# steering-wheel.net
KiCad netlist of a schematic drawn in Altium Designer
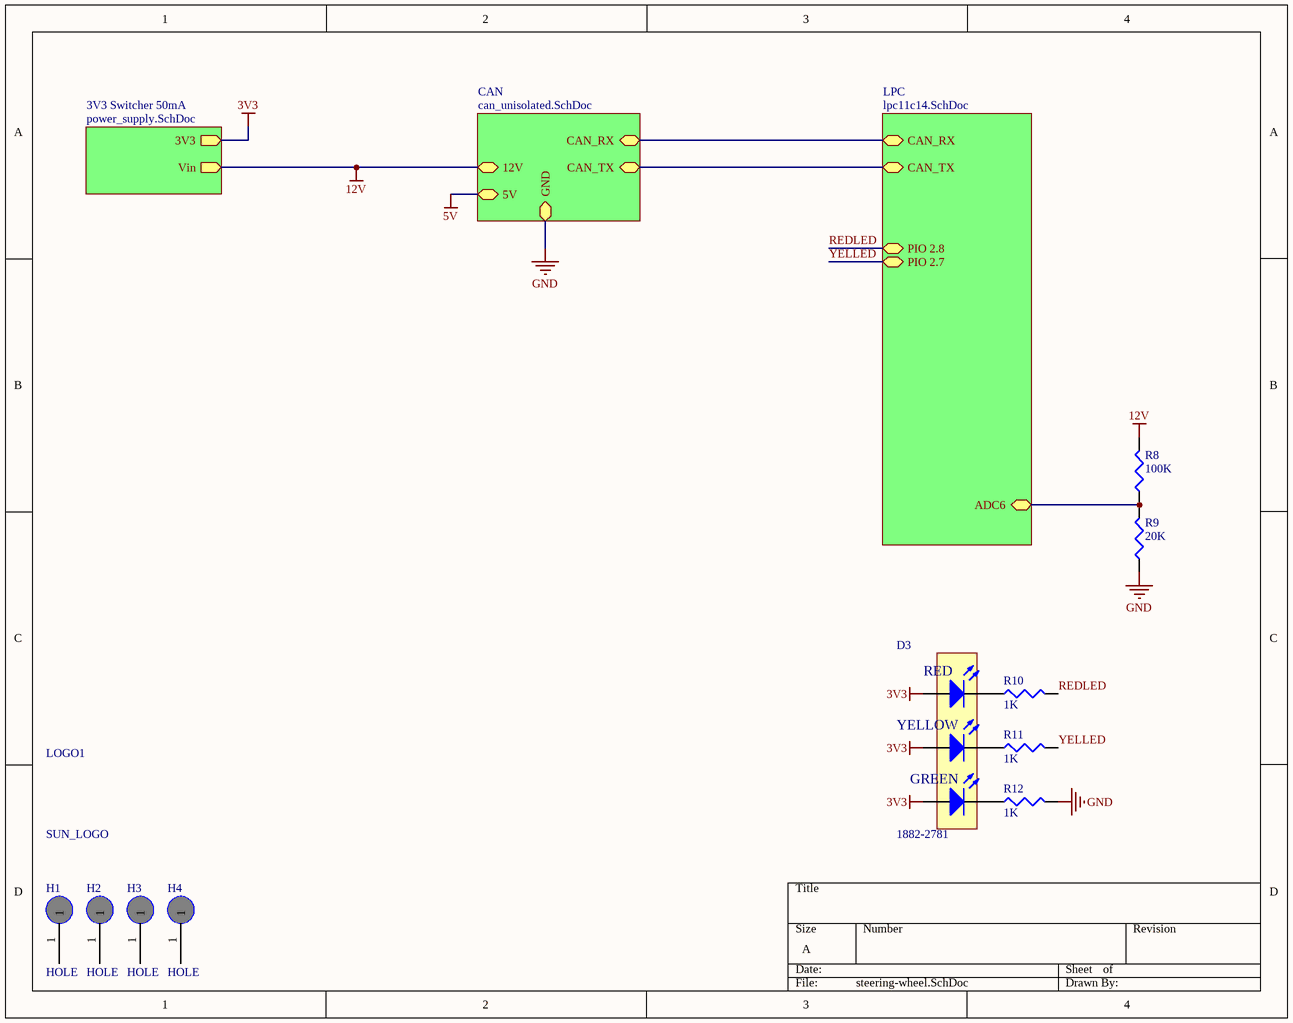
[diagram p0: steering-wheel.SchDoc]

(export (version "E")
  (design (tool "Eeschema 10.0.6"))
  (components
    (comp (ref "D3")
      (value "1882-2781")
      (footprint "LED_TRILEVEL")
      (description "Three level LED")
      (libsource (lib "RCLDQ") (part "LED-TRILEVEL"))
    )
    (comp (ref "H1")
      (value "HOLE")
      (footprint "M2.5")
      (description "Hole")
      (libsource (lib "Miscellaneous") (part "HOLE"))
    )
    (comp (ref "H2")
      (value "HOLE")
      (footprint "M2.5")
      (description "Hole")
      (libsource (lib "Miscellaneous") (part "HOLE"))
    )
    (comp (ref "H3")
      (value "HOLE")
      (footprint "M2.5")
      (description "Hole")
      (libsource (lib "Miscellaneous") (part "HOLE"))
    )
    (comp (ref "H4")
      (value "HOLE")
      (footprint "M2.5")
      (description "Hole")
      (libsource (lib "Miscellaneous") (part "HOLE"))
    )
    (comp (ref "LOGO1")
      (value "SUN_LOGO")
      (footprint "SUNSWIFTLOGO")
      (libsource (lib "Miscellaneous") (part "SUN_LOGO"))
    )
    (comp (ref "R8")
      (value "100K")
      (footprint "0603")
      (description "Resistor")
      (libsource (lib "2009_BatteryMaster") (part "RES1"))
    )
    (comp (ref "R9")
      (value "20K")
      (footprint "0603")
      (description "Resistor")
      (libsource (lib "2009_BatteryMaster") (part "RES1"))
    )
    (comp (ref "R10")
      (value "1K")
      (footprint "0603")
      (description "Resistor")
      (libsource (lib "RCLDQ") (part "RES1"))
    )
    (comp (ref "R11")
      (value "1K")
      (footprint "0603")
      (description "Resistor")
      (libsource (lib "RCLDQ") (part "RES1"))
    )
    (comp (ref "R12")
      (value "1K")
      (footprint "0603")
      (description "Resistor")
      (libsource (lib "RCLDQ") (part "RES1"))
    )
  )
  (nets
    (net (code "1") (name "/ADC6") (class "Default")
      (node (ref "R8") (pin "1") (pinfunction "1_1") (pintype "passive"))
      (node (ref "R9") (pin "2") (pinfunction "2_2") (pintype "passive"))
    )
    (net (code "4") (name "/REDLED") (class "Default")
      (node (ref "R10") (pin "2") (pinfunction "2_2") (pintype "passive"))
    )
    (net (code "5") (name "/YELLED") (class "Default")
      (node (ref "R11") (pin "2") (pinfunction "2_2") (pintype "passive"))
    )
    (net (code "6") (name "3V3") (class "Default")
      (node (ref "D3") (pin "4") (pinfunction "A_4") (pintype "passive"))
      (node (ref "D3") (pin "5") (pinfunction "A_5") (pintype "passive"))
      (node (ref "D3") (pin "6") (pinfunction "A_6") (pintype "passive"))
    )
    (net (code "8") (name "12V") (class "Default")
      (node (ref "R8") (pin "2") (pinfunction "2_2") (pintype "passive"))
    )
    (net (code "9") (name "GND") (class "Default")
      (node (ref "R12") (pin "2") (pinfunction "2_2") (pintype "passive"))
      (node (ref "R9") (pin "1") (pinfunction "1_1") (pintype "passive"))
    )
    (net (code "10") (name "Net-(D3-K-Pad1)") (class "Default")
      (node (ref "D3") (pin "1") (pinfunction "K_1") (pintype "passive"))
      (node (ref "R12") (pin "1") (pinfunction "1_1") (pintype "passive"))
    )
    (net (code "11") (name "Net-(D3-K-Pad2)") (class "Default")
      (node (ref "D3") (pin "2") (pinfunction "K_2") (pintype "passive"))
      (node (ref "R11") (pin "1") (pinfunction "1_1") (pintype "passive"))
    )
    (net (code "12") (name "Net-(D3-K-Pad3)") (class "Default")
      (node (ref "D3") (pin "3") (pinfunction "K_3") (pintype "passive"))
      (node (ref "R10") (pin "1") (pinfunction "1_1") (pintype "passive"))
    )
    (net (code "13") (name "unconnected-(H1-Pad1)") (class "Default")
      (node (ref "H1") (pin "1") (pinfunction "1_1") (pintype "passive"))
    )
    (net (code "14") (name "unconnected-(H2-Pad1)") (class "Default")
      (node (ref "H2") (pin "1") (pinfunction "1_1") (pintype "passive"))
    )
    (net (code "15") (name "unconnected-(H3-Pad1)") (class "Default")
      (node (ref "H3") (pin "1") (pinfunction "1_1") (pintype "passive"))
    )
    (net (code "16") (name "unconnected-(H4-Pad1)") (class "Default")
      (node (ref "H4") (pin "1") (pinfunction "1_1") (pintype "passive"))
    )
  )
)
